# Telemetry.net
KiCad netlist of a schematic drawn in Altium Designer
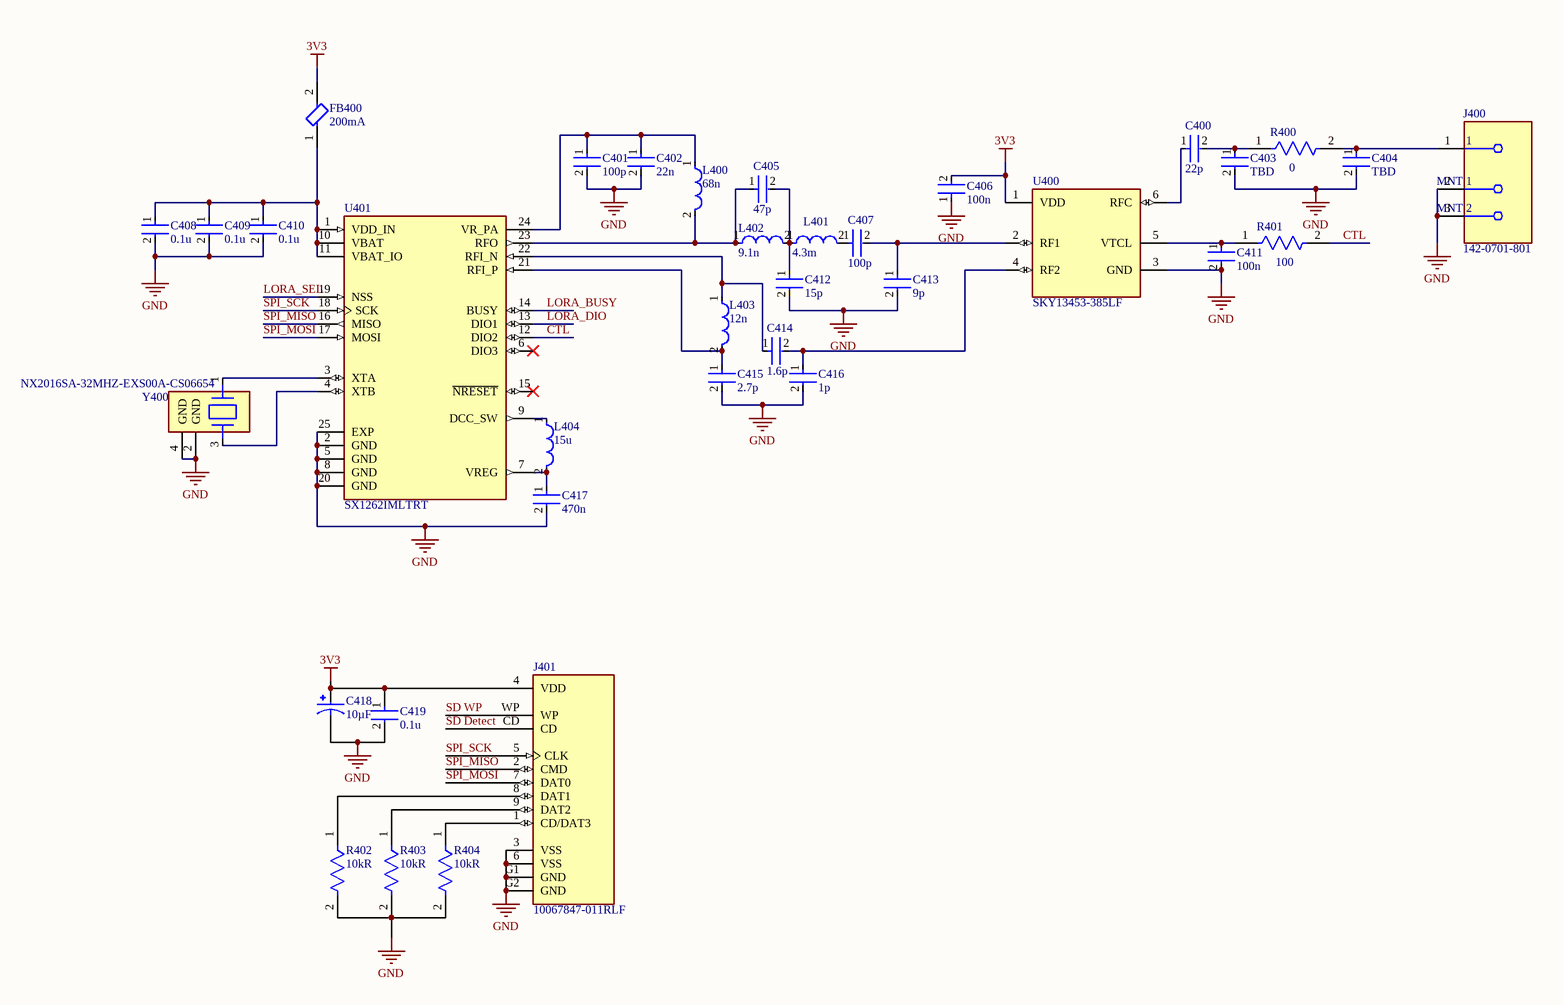
[diagram p0: Telemetry.SchDoc]

(export (version "E")
  (design (tool "Eeschema 10.0.6"))
  (components
    (comp (ref "C400")
      (value "CL10C681JB8NFNC")
      (footprint "FP-CL10-IPC_A")
      (description "Cap Ceramic 680pF 50V C0G ±5% Pad SMD 0603 +125°C T/R")
      (fields (field (name "CAPACITANCE") "22p") (field (name "TOLERANCE") "5%"))
      (libsource (lib "Altium Content Vault") (part "b4654b650e69147ec39a6b967a45e02"))
    )
    (comp (ref "C401")
      (value "CL10C681JB8NFNC")
      (footprint "FP-CL10-IPC_A")
      (description "Cap Ceramic 680pF 50V C0G ±5% Pad SMD 0603 +125°C T/R")
      (fields (field (name "CAPACITANCE") "100p") (field (name "TOLERANCE") "5%"))
      (libsource (lib "Altium Content Vault") (part "b4654b650e69147ec39a6b967a45e02"))
    )
    (comp (ref "C402")
      (value "CL10C681JB8NFNC")
      (footprint "FP-CL10-IPC_A")
      (description "Cap Ceramic 680pF 50V C0G ±5% Pad SMD 0603 +125°C T/R")
      (fields (field (name "CAPACITANCE") "22n") (field (name "TOLERANCE") "5%"))
      (libsource (lib "Altium Content Vault") (part "b4654b650e69147ec39a6b967a45e02"))
    )
    (comp (ref "C403")
      (value "CL10C681JB8NFNC")
      (footprint "FP-CL10-IPC_A")
      (description "Cap Ceramic 680pF 50V C0G ±5% Pad SMD 0603 +125°C T/R")
      (fields (field (name "CAPACITANCE") "TBD") (field (name "TOLERANCE") "5%"))
      (libsource (lib "Altium Content Vault") (part "b4654b650e69147ec39a6b967a45e02"))
    )
    (comp (ref "C404")
      (value "CL10C681JB8NFNC")
      (footprint "FP-CL10-IPC_A")
      (description "Cap Ceramic 680pF 50V C0G ±5% Pad SMD 0603 +125°C T/R")
      (fields (field (name "CAPACITANCE") "TBD") (field (name "TOLERANCE") "5%"))
      (libsource (lib "Altium Content Vault") (part "b4654b650e69147ec39a6b967a45e02"))
    )
    (comp (ref "C405")
      (value "CL10C681JB8NFNC")
      (footprint "FP-CL10-IPC_A")
      (description "Cap Ceramic 680pF 50V C0G ±5% Pad SMD 0603 +125°C T/R")
      (fields (field (name "CAPACITANCE") "47p") (field (name "TOLERANCE") "5%"))
      (libsource (lib "Altium Content Vault") (part "b4654b650e69147ec39a6b967a45e02"))
    )
    (comp (ref "C406")
      (value "CL10C681JB8NFNC")
      (footprint "FP-CL10-IPC_A")
      (description "Cap Ceramic 680pF 50V C0G ±5% Pad SMD 0603 +125°C T/R")
      (fields (field (name "CAPACITANCE") "100n") (field (name "TOLERANCE") "5%"))
      (libsource (lib "Altium Content Vault") (part "b4654b650e69147ec39a6b967a45e02"))
    )
    (comp (ref "C407")
      (value "CL10C681JB8NFNC")
      (footprint "FP-CL10-IPC_A")
      (description "Cap Ceramic 680pF 50V C0G ±5% Pad SMD 0603 +125°C T/R")
      (fields (field (name "CAPACITANCE") "100p") (field (name "TOLERANCE") "5%"))
      (libsource (lib "Altium Content Vault") (part "b4654b650e69147ec39a6b967a45e02"))
    )
    (comp (ref "C408")
      (value "CL10C681JB8NFNC")
      (footprint "FP-CL10-IPC_A")
      (description "Cap Ceramic 680pF 50V C0G ±5% Pad SMD 0603 +125°C T/R")
      (fields (field (name "CAPACITANCE") "0.1u") (field (name "TOLERANCE") "5%"))
      (libsource (lib "Altium Content Vault") (part "b4654b650e69147ec39a6b967a45e02"))
    )
    (comp (ref "C409")
      (value "CL10C681JB8NFNC")
      (footprint "FP-CL10-IPC_A")
      (description "Cap Ceramic 680pF 50V C0G ±5% Pad SMD 0603 +125°C T/R")
      (fields (field (name "CAPACITANCE") "0.1u") (field (name "TOLERANCE") "5%"))
      (libsource (lib "Altium Content Vault") (part "b4654b650e69147ec39a6b967a45e02"))
    )
    (comp (ref "C410")
      (value "CL10C681JB8NFNC")
      (footprint "FP-CL10-IPC_A")
      (description "Cap Ceramic 680pF 50V C0G ±5% Pad SMD 0603 +125°C T/R")
      (fields (field (name "CAPACITANCE") "0.1u") (field (name "TOLERANCE") "5%"))
      (libsource (lib "Altium Content Vault") (part "b4654b650e69147ec39a6b967a45e02"))
    )
    (comp (ref "C411")
      (value "CL10C681JB8NFNC")
      (footprint "FP-CL10-IPC_A")
      (description "Cap Ceramic 680pF 50V C0G ±5% Pad SMD 0603 +125°C T/R")
      (fields (field (name "CAPACITANCE") "100n") (field (name "TOLERANCE") "5%"))
      (libsource (lib "Altium Content Vault") (part "b4654b650e69147ec39a6b967a45e02"))
    )
    (comp (ref "C412")
      (value "CL10C681JB8NFNC")
      (footprint "FP-CL10-IPC_A")
      (description "Cap Ceramic 680pF 50V C0G ±5% Pad SMD 0603 +125°C T/R")
      (fields (field (name "CAPACITANCE") "15p") (field (name "TOLERANCE") "5%"))
      (libsource (lib "Altium Content Vault") (part "b4654b650e69147ec39a6b967a45e02"))
    )
    (comp (ref "C413")
      (value "CL10C681JB8NFNC")
      (footprint "FP-CL10-IPC_A")
      (description "Cap Ceramic 680pF 50V C0G ±5% Pad SMD 0603 +125°C T/R")
      (fields (field (name "CAPACITANCE") "9p") (field (name "TOLERANCE") "5%"))
      (libsource (lib "Altium Content Vault") (part "b4654b650e69147ec39a6b967a45e02"))
    )
    (comp (ref "C414")
      (value "CL10C681JB8NFNC")
      (footprint "FP-CL10-IPC_A")
      (description "Cap Ceramic 680pF 50V C0G ±5% Pad SMD 0603 +125°C T/R")
      (fields (field (name "CAPACITANCE") "1.6p") (field (name "TOLERANCE") "5%"))
      (libsource (lib "Altium Content Vault") (part "b4654b650e69147ec39a6b967a45e02"))
    )
    (comp (ref "C415")
      (value "CL10C681JB8NFNC")
      (footprint "FP-CL10-IPC_A")
      (description "Cap Ceramic 680pF 50V C0G ±5% Pad SMD 0603 +125°C T/R")
      (fields (field (name "CAPACITANCE") "2.7p") (field (name "TOLERANCE") "5%"))
      (libsource (lib "Altium Content Vault") (part "b4654b650e69147ec39a6b967a45e02"))
    )
    (comp (ref "C416")
      (value "CL10C681JB8NFNC")
      (footprint "FP-CL10-IPC_A")
      (description "Cap Ceramic 680pF 50V C0G ±5% Pad SMD 0603 +125°C T/R")
      (fields (field (name "CAPACITANCE") "1p") (field (name "TOLERANCE") "5%"))
      (libsource (lib "Altium Content Vault") (part "b4654b650e69147ec39a6b967a45e02"))
    )
    (comp (ref "C417")
      (value "CL10C681JB8NFNC")
      (footprint "FP-CL10-IPC_A")
      (description "Cap Ceramic 680pF 50V C0G ±5% Pad SMD 0603 +125°C T/R")
      (fields (field (name "CAPACITANCE") "470n") (field (name "TOLERANCE") "5%"))
      (libsource (lib "Altium Content Vault") (part "b4654b650e69147ec39a6b967a45e02"))
    )
    (comp (ref "C418")
      (value "10µF")
      (footprint "CAP_EEEFN1C100R")
      (description "10ÂµF 16V Aluminum Electrolytic Capacitors Radial, Can - SMD 1.35Ohm @ 100kHz 2000 Hrs @ 105Â°C")
      (fields (field (name "DIGI-KEY_PART_NUMBER") "10-EEE-FN1C100RCT-ND") (field (name "MP") "EEEFN1C100R"))
      (libsource (lib "Erich Robb") (part "EEEFN1C100R"))
    )
    (comp (ref "C419")
      (value "CL10C681JB8NFNC")
      (footprint "FP-CL10-IPC_A")
      (description "Cap Ceramic 680pF 50V C0G ±5% Pad SMD 0603 +125°C T/R")
      (fields (field (name "CAPACITANCE") "0.1u") (field (name "TOLERANCE") "5%"))
      (libsource (lib "Altium Content Vault") (part "b4654b650e69147ec39a6b967a45e02"))
    )
    (comp (ref "FB400")
      (value "200mA")
      (footprint "FP-BLM18-0_15-t0_8-IPC_B")
      (description "Chip Ferrite Bead, 0603, 120Ω @ 100MHz, 0.4Ω, 25%, 300mA")
      (fields (field (name "TOLERANCE") "25%"))
      (libsource (lib "Altium Content Vault") (part "5f30dd21d616792df468990f7003faa"))
    )
    (comp (ref "J400")
      (value "142-0701-801")
      (footprint "FP-142-0701-801-MFG")
      (description "CONN SMA JACK STR 50OHM EDGE MNT")
      (libsource (lib "Altium Content Vault") (part "89929399afe843c8b6880c6cbd0f99a"))
    )
    (comp (ref "J401")
      (value "10067847-011RLF")
      (footprint "AMPHENOL_10067847-011RLF")
      (description "SD card reader Push - Push Type")
      (fields (field (name "MF") "Amphenol FCI"))
      (libsource (lib "Erich Robb") (part "10067847-011RLF"))
    )
    (comp (ref "L400")
      (value "68n")
      (footprint "FP-LQM18NN_00-IPC_B")
      (description "Multilayer Type Inductor for General Circuits, 0603 (1608), 2200nH, 10%, 1.15Ω, 15mA")
      (fields (field (name "TOLERANCE") "10%"))
      (libsource (lib "Altium Content Vault") (part "725321dda6339637d4d059423bc1c3c"))
    )
    (comp (ref "L401")
      (value "4.3m")
      (footprint "FP-LQM18NN_00-IPC_B")
      (description "Multilayer Type Inductor for General Circuits, 0603 (1608), 2200nH, 10%, 1.15Ω, 15mA")
      (fields (field (name "TOLERANCE") "10%"))
      (libsource (lib "Altium Content Vault") (part "725321dda6339637d4d059423bc1c3c"))
    )
    (comp (ref "L402")
      (value "9.1n")
      (footprint "FP-LQM18NN_00-IPC_B")
      (description "Multilayer Type Inductor for General Circuits, 0603 (1608), 2200nH, 10%, 1.15Ω, 15mA")
      (fields (field (name "TOLERANCE") "10%"))
      (libsource (lib "Altium Content Vault") (part "725321dda6339637d4d059423bc1c3c"))
    )
    (comp (ref "L403")
      (value "12n")
      (footprint "FP-LQM18NN_00-IPC_B")
      (description "Multilayer Type Inductor for General Circuits, 0603 (1608), 2200nH, 10%, 1.15Ω, 15mA")
      (fields (field (name "TOLERANCE") "10%"))
      (libsource (lib "Altium Content Vault") (part "725321dda6339637d4d059423bc1c3c"))
    )
    (comp (ref "L404")
      (value "15u")
      (footprint "FP-LQM18NN_00-IPC_B")
      (description "Multilayer Type Inductor for General Circuits, 0603 (1608), 2200nH, 10%, 1.15Ω, 15mA")
      (fields (field (name "TOLERANCE") "10%"))
      (libsource (lib "Altium Content Vault") (part "725321dda6339637d4d059423bc1c3c"))
    )
    (comp (ref "R400")
      (value "0")
      (footprint "FP-CPF0603-MFG")
      (description "RES SMD 2.15KΩ 0.1% 1/16W 0603")
      (fields
        (field (name "MANUFACTURER") "TE Connectivity")
        (field (name "OCTOPART") "https://octopart.com/cpf0603b2k15e1-te+connectivity-22739551")
      )
      (libsource (lib "Altium Content Vault") (part "1029c3af85768c4190bb7ad29bc67b5"))
    )
    (comp (ref "R401")
      (value "100")
      (footprint "FP-CPF0603-MFG")
      (description "RES SMD 2.15KΩ 0.1% 1/16W 0603")
      (fields
        (field (name "MANUFACTURER") "TE Connectivity")
        (field (name "OCTOPART") "https://octopart.com/cpf0603b2k15e1-te+connectivity-22739551")
      )
      (libsource (lib "Altium Content Vault") (part "1029c3af85768c4190bb7ad29bc67b5"))
    )
    (comp (ref "R402")
      (value "10kR")
      (footprint "FP-CPF0603-MFG")
      (description "RES SMD 2.15KΩ 0.1% 1/16W 0603")
      (fields
        (field (name "MANUFACTURER") "TE Connectivity")
        (field (name "OCTOPART") "https://octopart.com/cpf0603b2k15e1-te+connectivity-22739551")
      )
      (libsource (lib "Altium Content Vault") (part "1029c3af85768c4190bb7ad29bc67b5"))
    )
    (comp (ref "R403")
      (value "10kR")
      (footprint "FP-CPF0603-MFG")
      (description "RES SMD 2.15KΩ 0.1% 1/16W 0603")
      (fields
        (field (name "MANUFACTURER") "TE Connectivity")
        (field (name "OCTOPART") "https://octopart.com/cpf0603b2k15e1-te+connectivity-22739551")
      )
      (libsource (lib "Altium Content Vault") (part "1029c3af85768c4190bb7ad29bc67b5"))
    )
    (comp (ref "R404")
      (value "10kR")
      (footprint "FP-CPF0603-MFG")
      (description "RES SMD 2.15KΩ 0.1% 1/16W 0603")
      (fields
        (field (name "MANUFACTURER") "TE Connectivity")
        (field (name "OCTOPART") "https://octopart.com/cpf0603b2k15e1-te+connectivity-22739551")
      )
      (libsource (lib "Altium Content Vault") (part "1029c3af85768c4190bb7ad29bc67b5"))
    )
    (comp (ref "U400")
      (value "SKY13453-385LF")
      (footprint "IC_SKY13453-385LF")
      (description "RF Switch IC WLAN SPDT 6 GHz 50Ohm 6-QFN (1x1)")
      (fields (field (name "MF") "Skyworks Solutions"))
      (libsource (lib "Colin Sutter") (part "SKY13453-385LF"))
    )
    (comp (ref "U401")
      (value "SX1262IMLTRT")
      (footprint "QFN50P400X400X100-25N")
      (description "IC RF TxRx Only General ISM < 1GHz LoRaWAN 150MHz ~ 960MHz 24-VFQFN Exposed Pad")
      (fields (field (name "MF") "Semtech Corporation"))
      (libsource (lib "Colin Sutter") (part "SX1262IMLTRT"))
    )
    (comp (ref "Y400")
      (value "NX2016SA-32MHZ-EXS00A-CS06654")
      (footprint "FP-NX2016SA-MFG")
      (description "CRYSTAL 32.0000MHZ 8PF SMD")
      (libsource (lib "Altium Content Vault") (part "0d11ad3ca7be055efd3b4f344707230"))
    )
  )
  (nets
    (net (code "1") (name "/CTL") (class "Default")
      (node (ref "R401") (pin "2") (pinfunction "2_2") (pintype "passive"))
      (node (ref "U401") (pin "12") (pinfunction "DIO2_12") (pintype "bidirectional"))
    )
    (net (code "2") (name "/LORA_BUSY") (class "Default")
      (node (ref "U401") (pin "14") (pinfunction "BUSY_14") (pintype "bidirectional"))
    )
    (net (code "3") (name "/LORA_DIO") (class "Default")
      (node (ref "U401") (pin "13") (pinfunction "DIO1_13") (pintype "bidirectional"))
    )
    (net (code "4") (name "/LORA_SEL") (class "Default")
      (node (ref "U401") (pin "19") (pinfunction "NSS_19") (pintype "input"))
    )
    (net (code "5") (name "/SD Detect") (class "Default")
      (node (ref "J401") (pin "CD") (pinfunction "CD_CD") (pintype "passive"))
    )
    (net (code "6") (name "/SD WP") (class "Default")
      (node (ref "J401") (pin "WP") (pinfunction "WP_WP") (pintype "passive"))
    )
    (net (code "7") (name "/SPI_MISO") (class "Default")
      (node (ref "J401") (pin "2") (pinfunction "CMD_2") (pintype "bidirectional"))
      (node (ref "U401") (pin "16") (pinfunction "MISO_16") (pintype "output"))
    )
    (net (code "8") (name "/SPI_MOSI") (class "Default")
      (node (ref "J401") (pin "7") (pinfunction "DAT0_7") (pintype "bidirectional"))
      (node (ref "U401") (pin "17") (pinfunction "MOSI_17") (pintype "input"))
    )
    (net (code "9") (name "/SPI_SCK") (class "Default")
      (node (ref "J401") (pin "5") (pinfunction "CLK_5") (pintype "input"))
      (node (ref "U401") (pin "18") (pinfunction "SCK_18") (pintype "input"))
    )
    (net (code "10") (name "3V3") (class "Default")
      (node (ref "C406") (pin "2") (pinfunction "2_2") (pintype "passive"))
      (node (ref "C418") (pin "1") (pinfunction "1_1") (pintype "passive"))
      (node (ref "C419") (pin "1") (pinfunction "1_1") (pintype "passive"))
      (node (ref "FB400") (pin "2") (pinfunction "2_2") (pintype "passive"))
      (node (ref "J401") (pin "4") (pinfunction "VDD_4") (pintype "power_in"))
      (node (ref "U400") (pin "1") (pinfunction "VDD_1") (pintype "power_in"))
    )
    (net (code "11") (name "GND") (class "Default")
      (node (ref "C401") (pin "2") (pinfunction "2_2") (pintype "passive"))
      (node (ref "C402") (pin "2") (pinfunction "2_2") (pintype "passive"))
      (node (ref "C403") (pin "2") (pinfunction "2_2") (pintype "passive"))
      (node (ref "C404") (pin "2") (pinfunction "2_2") (pintype "passive"))
      (node (ref "C406") (pin "1") (pinfunction "1_1") (pintype "passive"))
      (node (ref "C408") (pin "2") (pinfunction "2_2") (pintype "passive"))
      (node (ref "C409") (pin "2") (pinfunction "2_2") (pintype "passive"))
      (node (ref "C410") (pin "2") (pinfunction "2_2") (pintype "passive"))
      (node (ref "C411") (pin "2") (pinfunction "2_2") (pintype "passive"))
      (node (ref "C412") (pin "2") (pinfunction "2_2") (pintype "passive"))
      (node (ref "C413") (pin "2") (pinfunction "2_2") (pintype "passive"))
      (node (ref "C415") (pin "2") (pinfunction "2_2") (pintype "passive"))
      (node (ref "C416") (pin "2") (pinfunction "2_2") (pintype "passive"))
      (node (ref "C417") (pin "2") (pinfunction "2_2") (pintype "passive"))
      (node (ref "C418") (pin "2") (pinfunction "2_2") (pintype "passive"))
      (node (ref "C419") (pin "2") (pinfunction "2_2") (pintype "passive"))
      (node (ref "J400") (pin "2") (pinfunction "MNT_1_2") (pintype "passive"))
      (node (ref "J400") (pin "3") (pinfunction "MNT_2_3") (pintype "passive"))
      (node (ref "J401") (pin "3") (pinfunction "VSS_3") (pintype "power_in"))
      (node (ref "J401") (pin "6") (pinfunction "VSS_6") (pintype "power_in"))
      (node (ref "J401") (pin "G1") (pinfunction "GND_G1") (pintype "power_in"))
      (node (ref "J401") (pin "G2") (pinfunction "GND_G2") (pintype "power_in"))
      (node (ref "R402") (pin "2") (pinfunction "2_2") (pintype "passive"))
      (node (ref "R403") (pin "2") (pinfunction "2_2") (pintype "passive"))
      (node (ref "R404") (pin "2") (pinfunction "2_2") (pintype "passive"))
      (node (ref "U400") (pin "3") (pinfunction "GND_3") (pintype "power_in"))
      (node (ref "U401") (pin "2") (pinfunction "GND_2") (pintype "power_in"))
      (node (ref "U401") (pin "20") (pinfunction "GND_20") (pintype "power_in"))
      (node (ref "U401") (pin "25") (pinfunction "EXP_25") (pintype "power_in"))
      (node (ref "U401") (pin "5") (pinfunction "GND_5") (pintype "power_in"))
      (node (ref "U401") (pin "8") (pinfunction "GND_8") (pintype "power_in"))
      (node (ref "Y400") (pin "2") (pinfunction "GND_2") (pintype "power_in"))
      (node (ref "Y400") (pin "4") (pinfunction "GND_4") (pintype "power_in"))
    )
    (net (code "12") (name "Net-(C400-Pad2)") (class "Default")
      (node (ref "C400") (pin "2") (pinfunction "2_2") (pintype "passive"))
      (node (ref "C403") (pin "1") (pinfunction "1_1") (pintype "passive"))
      (node (ref "R400") (pin "1") (pinfunction "1_1") (pintype "passive"))
    )
    (net (code "13") (name "Net-(C404-Pad1)") (class "Default")
      (node (ref "C404") (pin "1") (pinfunction "1_1") (pintype "passive"))
      (node (ref "J400") (pin "1") (pinfunction "1_1") (pintype "passive"))
      (node (ref "R400") (pin "2") (pinfunction "2_2") (pintype "passive"))
    )
    (net (code "14") (name "Net-(C405-Pad2)") (class "Default")
      (node (ref "C405") (pin "2") (pinfunction "2_2") (pintype "passive"))
      (node (ref "C412") (pin "1") (pinfunction "1_1") (pintype "passive"))
      (node (ref "L401") (pin "1") (pinfunction "1_1") (pintype "passive"))
      (node (ref "L402") (pin "2") (pinfunction "2_2") (pintype "passive"))
    )
    (net (code "15") (name "Net-(C407-Pad1)") (class "Default")
      (node (ref "C407") (pin "1") (pinfunction "1_1") (pintype "passive"))
      (node (ref "L401") (pin "2") (pinfunction "2_2") (pintype "passive"))
    )
    (net (code "16") (name "Net-(J401-CD{slash}DAT3)") (class "Default")
      (node (ref "J401") (pin "1") (pinfunction "CD/DAT3_1") (pintype "bidirectional"))
      (node (ref "R404") (pin "1") (pinfunction "1_1") (pintype "passive"))
    )
    (net (code "17") (name "Net-(J401-DAT1)") (class "Default")
      (node (ref "J401") (pin "8") (pinfunction "DAT1_8") (pintype "bidirectional"))
      (node (ref "R402") (pin "1") (pinfunction "1_1") (pintype "passive"))
    )
    (net (code "18") (name "Net-(J401-DAT2)") (class "Default")
      (node (ref "J401") (pin "9") (pinfunction "DAT2_9") (pintype "bidirectional"))
      (node (ref "R403") (pin "1") (pinfunction "1_1") (pintype "passive"))
    )
    (net (code "19") (name "Net-(U400-RF1)") (class "Default")
      (node (ref "C407") (pin "2") (pinfunction "2_2") (pintype "passive"))
      (node (ref "C413") (pin "1") (pinfunction "1_1") (pintype "passive"))
      (node (ref "U400") (pin "2") (pinfunction "RF1_2") (pintype "bidirectional"))
    )
    (net (code "20") (name "Net-(U400-RF2)") (class "Default")
      (node (ref "C414") (pin "2") (pinfunction "2_2") (pintype "passive"))
      (node (ref "C416") (pin "1") (pinfunction "1_1") (pintype "passive"))
      (node (ref "U400") (pin "4") (pinfunction "RF2_4") (pintype "bidirectional"))
    )
    (net (code "21") (name "Net-(U400-RFC)") (class "Default")
      (node (ref "C400") (pin "1") (pinfunction "1_1") (pintype "passive"))
      (node (ref "U400") (pin "6") (pinfunction "RFC_6") (pintype "bidirectional"))
    )
    (net (code "22") (name "Net-(U400-VTCL)") (class "Default")
      (node (ref "C411") (pin "1") (pinfunction "1_1") (pintype "passive"))
      (node (ref "R401") (pin "1") (pinfunction "1_1") (pintype "passive"))
      (node (ref "U400") (pin "5") (pinfunction "VTCL_5") (pintype "passive"))
    )
    (net (code "23") (name "Net-(U401-DCC_SW)") (class "Default")
      (node (ref "L404") (pin "1") (pinfunction "1_1") (pintype "passive"))
      (node (ref "U401") (pin "9") (pinfunction "DCC_SW_9") (pintype "output"))
    )
    (net (code "24") (name "Net-(U401-RFI_N)") (class "Default")
      (node (ref "C414") (pin "1") (pinfunction "1_1") (pintype "passive"))
      (node (ref "L403") (pin "1") (pinfunction "1_1") (pintype "passive"))
      (node (ref "U401") (pin "22") (pinfunction "RFI_N_22") (pintype "input"))
    )
    (net (code "25") (name "Net-(U401-RFI_P)") (class "Default")
      (node (ref "C415") (pin "1") (pinfunction "1_1") (pintype "passive"))
      (node (ref "L403") (pin "2") (pinfunction "2_2") (pintype "passive"))
      (node (ref "U401") (pin "21") (pinfunction "RFI_P_21") (pintype "input"))
    )
    (net (code "26") (name "Net-(U401-RFO)") (class "Default")
      (node (ref "C405") (pin "1") (pinfunction "1_1") (pintype "passive"))
      (node (ref "L400") (pin "2") (pinfunction "2_2") (pintype "passive"))
      (node (ref "L402") (pin "1") (pinfunction "1_1") (pintype "passive"))
      (node (ref "U401") (pin "23") (pinfunction "RFO_23") (pintype "output"))
    )
    (net (code "27") (name "Net-(U401-VBAT)") (class "Default")
      (node (ref "C408") (pin "1") (pinfunction "1_1") (pintype "passive"))
      (node (ref "C409") (pin "1") (pinfunction "1_1") (pintype "passive"))
      (node (ref "C410") (pin "1") (pinfunction "1_1") (pintype "passive"))
      (node (ref "FB400") (pin "1") (pinfunction "1_1") (pintype "passive"))
      (node (ref "U401") (pin "1") (pinfunction "VDD_IN_1") (pintype "input"))
      (node (ref "U401") (pin "10") (pinfunction "VBAT_10") (pintype "power_in"))
      (node (ref "U401") (pin "11") (pinfunction "VBAT_IO_11") (pintype "power_in"))
    )
    (net (code "28") (name "Net-(U401-VREG)") (class "Default")
      (node (ref "C417") (pin "1") (pinfunction "1_1") (pintype "passive"))
      (node (ref "L404") (pin "2") (pinfunction "2_2") (pintype "passive"))
      (node (ref "U401") (pin "7") (pinfunction "VREG_7") (pintype "output"))
    )
    (net (code "29") (name "Net-(U401-VR_PA)") (class "Default")
      (node (ref "C401") (pin "1") (pinfunction "1_1") (pintype "passive"))
      (node (ref "C402") (pin "1") (pinfunction "1_1") (pintype "passive"))
      (node (ref "L400") (pin "1") (pinfunction "1_1") (pintype "passive"))
      (node (ref "U401") (pin "24") (pinfunction "VR_PA_24") (pintype "power_in"))
    )
    (net (code "30") (name "Net-(U401-XTA)") (class "Default")
      (node (ref "U401") (pin "3") (pinfunction "XTA_3") (pintype "bidirectional"))
      (node (ref "Y400") (pin "1") (pinfunction "1_1") (pintype "passive"))
    )
    (net (code "31") (name "Net-(U401-XTB)") (class "Default")
      (node (ref "U401") (pin "4") (pinfunction "XTB_4") (pintype "bidirectional"))
      (node (ref "Y400") (pin "3") (pinfunction "3_3") (pintype "passive"))
    )
    (net (code "32") (name "unconnected-(U401-DIO3-Pad6)") (class "Default")
      (node (ref "U401") (pin "6") (pinfunction "DIO3_6") (pintype "bidirectional+no_connect"))
    )
    (net (code "33") (name "unconnected-(U401-~{NRESET}-Pad15)") (class "Default")
      (node (ref "U401") (pin "15") (pinfunction "~{NRESET}_15") (pintype "bidirectional+no_connect"))
    )
  )
)
